# ESP_SmartWatch.net
KiCad netlist of a schematic drawn in EAGLE
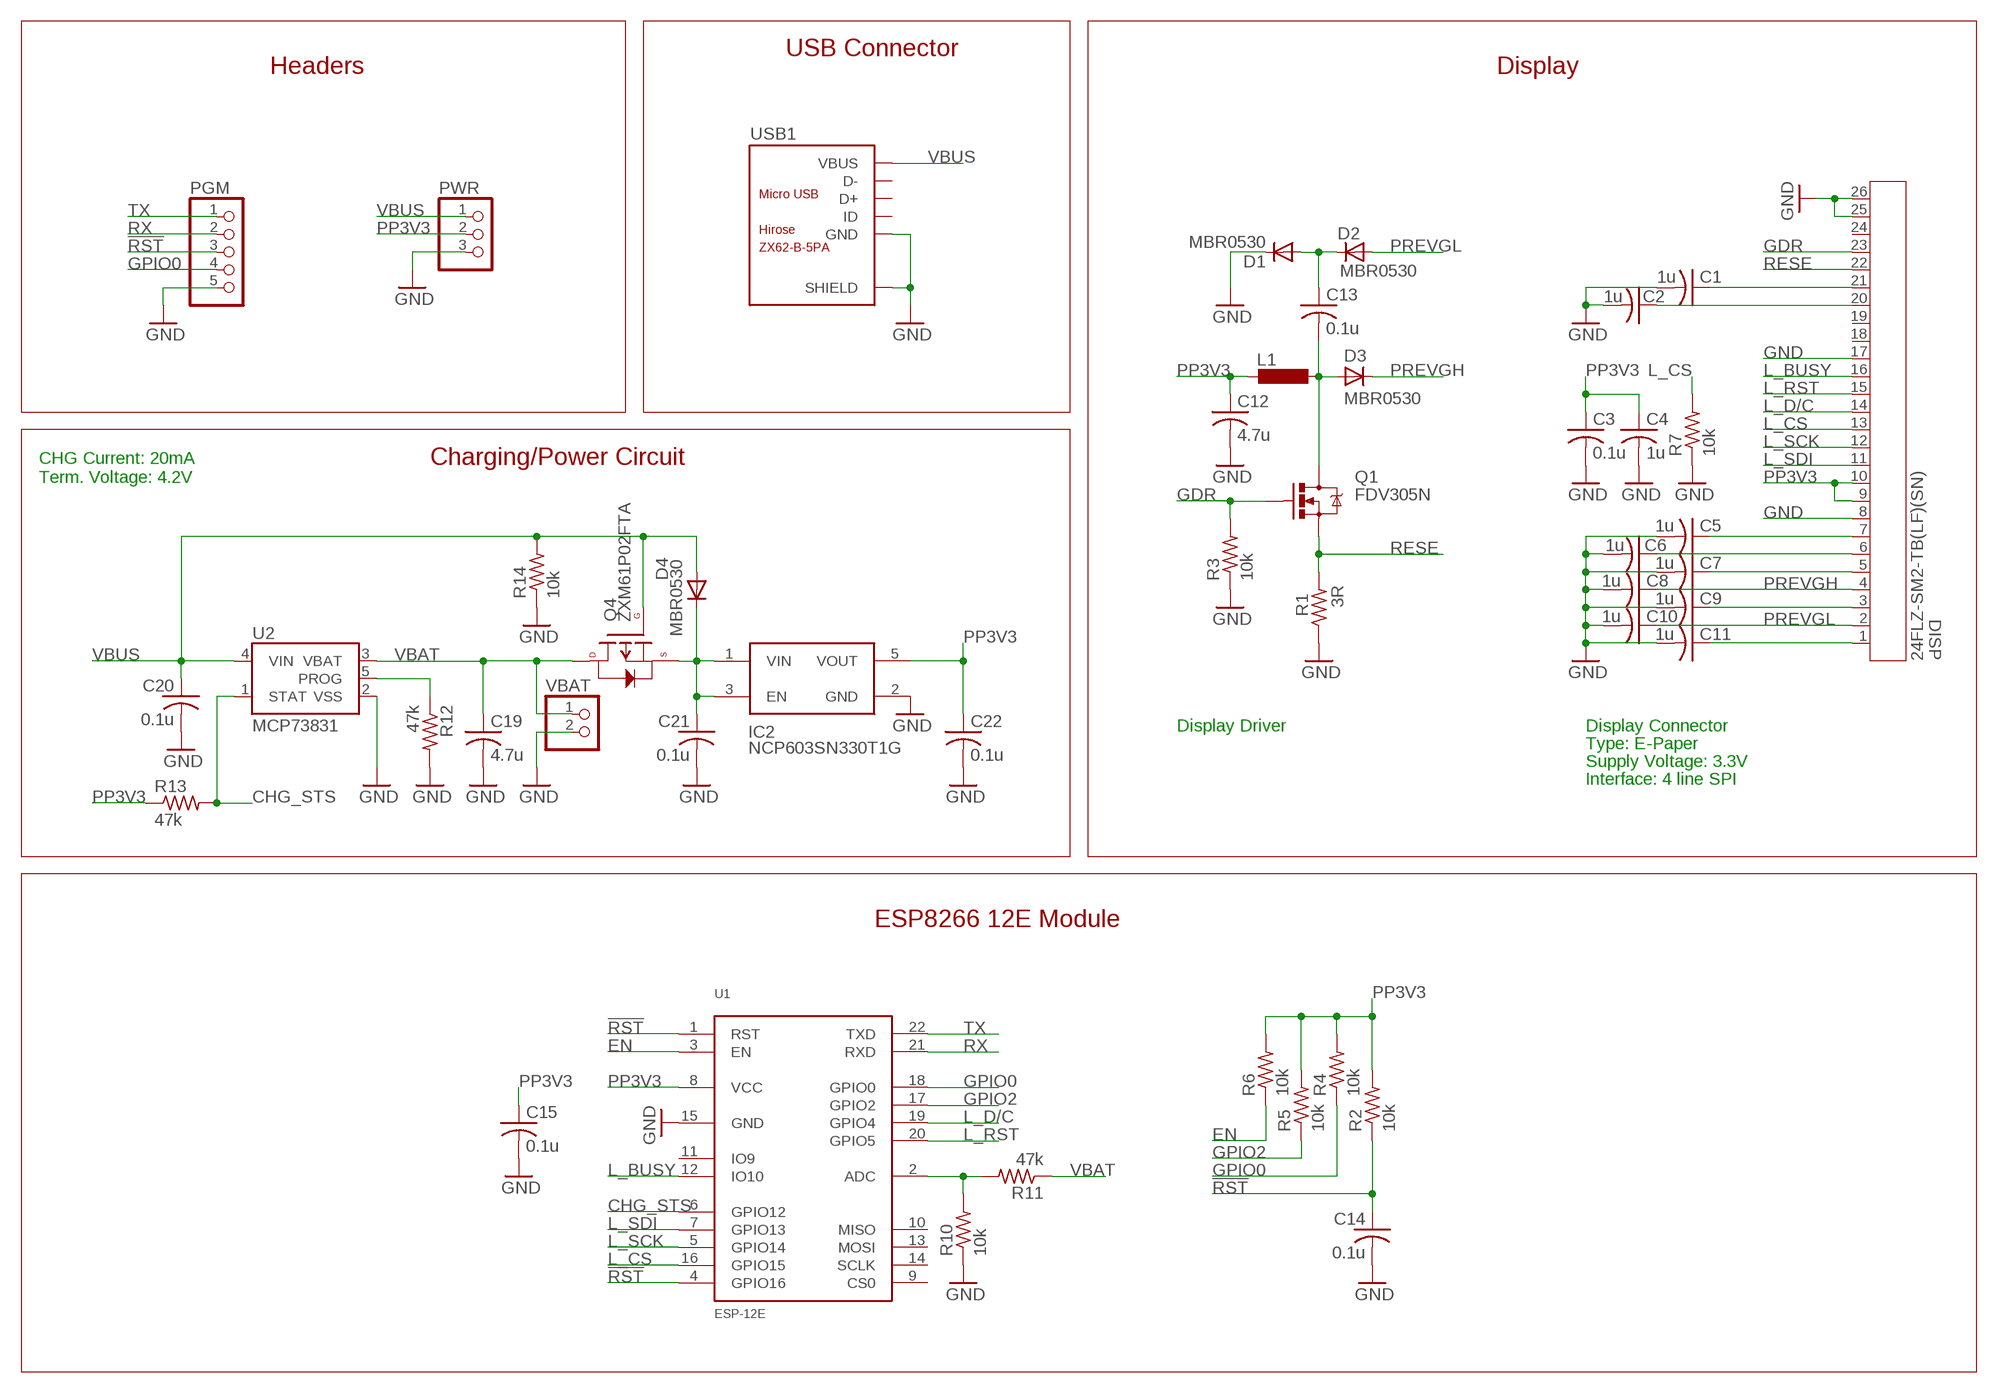
[diagram p0: schematic, sheet 1]

(export (version "E")
  (design (tool "Eeschema 10.0.6"))
  (components
    (comp (ref "C1")
      (value "1u")
      (footprint "eagle-import:C0603")
      (libsource (lib "eagle-import") (part "C-USC0603"))
    )
    (comp (ref "C2")
      (value "1u")
      (footprint "eagle-import:C0603")
      (libsource (lib "eagle-import") (part "C-USC0603"))
    )
    (comp (ref "C3")
      (value "0.1u")
      (footprint "eagle-import:C0603")
      (libsource (lib "eagle-import") (part "C-USC0603"))
    )
    (comp (ref "C4")
      (value "1u")
      (footprint "eagle-import:C0603")
      (libsource (lib "eagle-import") (part "C-USC0603"))
    )
    (comp (ref "C5")
      (value "1u")
      (footprint "eagle-import:C0603")
      (libsource (lib "eagle-import") (part "C-USC0603"))
    )
    (comp (ref "C6")
      (value "1u")
      (footprint "eagle-import:C0603")
      (libsource (lib "eagle-import") (part "C-USC0603"))
    )
    (comp (ref "C7")
      (value "1u")
      (footprint "eagle-import:C0603")
      (libsource (lib "eagle-import") (part "C-USC0603"))
    )
    (comp (ref "C8")
      (value "1u")
      (footprint "eagle-import:C0603")
      (libsource (lib "eagle-import") (part "C-USC0603"))
    )
    (comp (ref "C9")
      (value "1u")
      (footprint "eagle-import:C0603")
      (libsource (lib "eagle-import") (part "C-USC0603"))
    )
    (comp (ref "C10")
      (value "1u")
      (footprint "eagle-import:C0603")
      (libsource (lib "eagle-import") (part "C-USC0603"))
    )
    (comp (ref "C11")
      (value "1u")
      (footprint "eagle-import:C0603")
      (libsource (lib "eagle-import") (part "C-USC0603"))
    )
    (comp (ref "C12")
      (value "4.7u")
      (footprint "eagle-import:C0603")
      (libsource (lib "eagle-import") (part "C-USC0603"))
    )
    (comp (ref "C13")
      (value "0.1u")
      (footprint "eagle-import:C0603")
      (libsource (lib "eagle-import") (part "C-USC0603"))
    )
    (comp (ref "C14")
      (value "0.1u")
      (footprint "eagle-import:C0603")
      (libsource (lib "eagle-import") (part "C-USC0603"))
    )
    (comp (ref "C15")
      (value "0.1u")
      (footprint "eagle-import:C0603")
      (libsource (lib "eagle-import") (part "C-USC0603"))
    )
    (comp (ref "C19")
      (value "4.7u")
      (footprint "eagle-import:C0603")
      (libsource (lib "eagle-import") (part "C-USC0603"))
    )
    (comp (ref "C20")
      (value "0.1u")
      (footprint "eagle-import:C0603")
      (libsource (lib "eagle-import") (part "C-USC0603"))
    )
    (comp (ref "C21")
      (value "0.1u")
      (footprint "eagle-import:C0603")
      (libsource (lib "eagle-import") (part "C-USC0603"))
    )
    (comp (ref "C22")
      (value "0.1u")
      (footprint "eagle-import:C0603")
      (libsource (lib "eagle-import") (part "C-USC0603"))
    )
    (comp (ref "D1")
      (value "MBR0530")
      (footprint "eagle-import:SOD123")
      (libsource (lib "eagle-import") (part "MBR0520LT"))
    )
    (comp (ref "D2")
      (value "MBR0530")
      (footprint "eagle-import:SOD123")
      (libsource (lib "eagle-import") (part "MBR0520LT"))
    )
    (comp (ref "D3")
      (value "MBR0530")
      (footprint "eagle-import:SOD123")
      (libsource (lib "eagle-import") (part "MBR0520LT"))
    )
    (comp (ref "D4")
      (value "MBR0530")
      (footprint "eagle-import:SOD123")
      (libsource (lib "eagle-import") (part "MBR0520LT"))
    )
    (comp (ref "DISP")
      (value "24FLZ-SM2-TB(LF)(SN)")
      (footprint "eagle-import:CON24_1X24_DB_JST")
      (fields (field (name "MANUFACTURER_PART_NUMBER") "24FLZSM2TBLFSN"))
      (libsource (lib "eagle-import") (part "24FLZ-SM2-TB(LF)(SN)"))
    )
    (comp (ref "IC2")
      (value "NCP603SN330T1G")
      (footprint "eagle-import:SOT95P275X110-5N")
      (fields (field (name "RS_PART_NUMBER") "8051845P"))
      (libsource (lib "eagle-import") (part "NCP603SN330T1G"))
    )
    (comp (ref "L1")
      (value "ASPI-6045S-680M-T")
      (footprint "eagle-import:ASPI-6045S-680M-T")
      (libsource (lib "eagle-import") (part "ASPI-6045S-680M-T"))
    )
    (comp (ref "PGM")
      (value "PINHD-1X05_2.00")
      (footprint "eagle-import:1X05M")
      (libsource (lib "eagle-import") (part "PINHD-1X05_2.00"))
    )
    (comp (ref "PWR")
      (value "PINHD-1X03_2.00")
      (footprint "eagle-import:1X03M")
      (libsource (lib "eagle-import") (part "PINHD-1X03_2.00"))
    )
    (comp (ref "Q1")
      (value "FDV305N")
      (footprint "eagle-import:SOT23-3")
      (libsource (lib "eagle-import") (part "MOSFET-NCHANNELAO3404A"))
    )
    (comp (ref "Q4")
      (value "ZXM61P02FTA")
      (footprint "eagle-import:SOT23-3")
      (libsource (lib "eagle-import") (part "P-CHANNEL-MOSFET"))
    )
    (comp (ref "R1")
      (value "3R")
      (footprint "eagle-import:R0603")
      (libsource (lib "eagle-import") (part "R-US_R0603"))
    )
    (comp (ref "R2")
      (value "10k")
      (footprint "eagle-import:R0603")
      (libsource (lib "eagle-import") (part "R-US_R0603"))
    )
    (comp (ref "R3")
      (value "10k")
      (footprint "eagle-import:R0603")
      (libsource (lib "eagle-import") (part "R-US_R0603"))
    )
    (comp (ref "R4")
      (value "10k")
      (footprint "eagle-import:R0603")
      (libsource (lib "eagle-import") (part "R-US_R0603"))
    )
    (comp (ref "R5")
      (value "10k")
      (footprint "eagle-import:R0603")
      (libsource (lib "eagle-import") (part "R-US_R0603"))
    )
    (comp (ref "R6")
      (value "10k")
      (footprint "eagle-import:R0603")
      (libsource (lib "eagle-import") (part "R-US_R0603"))
    )
    (comp (ref "R7")
      (value "10k")
      (footprint "eagle-import:R0603")
      (libsource (lib "eagle-import") (part "R-US_R0603"))
    )
    (comp (ref "R10")
      (value "10k")
      (footprint "eagle-import:R0603")
      (libsource (lib "eagle-import") (part "R-US_R0603"))
    )
    (comp (ref "R11")
      (value "47k")
      (footprint "eagle-import:R0603")
      (libsource (lib "eagle-import") (part "R-US_R0603"))
    )
    (comp (ref "R12")
      (value "47k")
      (footprint "eagle-import:R0603")
      (libsource (lib "eagle-import") (part "R-US_R0603"))
    )
    (comp (ref "R13")
      (value "47k")
      (footprint "eagle-import:R0603")
      (libsource (lib "eagle-import") (part "R-US_R0603"))
    )
    (comp (ref "R14")
      (value "10k")
      (footprint "eagle-import:R0603")
      (libsource (lib "eagle-import") (part "R-US_R0603"))
    )
    (comp (ref "U1")
      (value "ESP-12E")
      (footprint "eagle-import:ESP-12F")
      (libsource (lib "eagle-import") (part "ESP-12F"))
    )
    (comp (ref "U2")
      (value "MCP73831")
      (footprint "eagle-import:SOT23-5")
      (libsource (lib "eagle-import") (part "MCP73831"))
    )
    (comp (ref "USB1")
      (value "ZX62-B-5PA")
      (footprint "eagle-import:MICRO-USB5+6P-SMD-0.65-AB")
      (libsource (lib "eagle-import") (part "MICRO-USB-SMD(ZX62-B-5PA)"))
    )
    (comp (ref "VBAT")
      (value "PINHD-1X02_2.00")
      (footprint "eagle-import:1X02M")
      (libsource (lib "eagle-import") (part "PINHD-1X02_2.00"))
    )
  )
  (nets
    (net (code "1") (name "/CHG_STS") (class "Default")
      (node (ref "R13") (pin "2") (pinfunction "2_2") (pintype "passive"))
      (node (ref "U1") (pin "6") (pinfunction "GPIO12_6") (pintype "bidirectional"))
      (node (ref "U2") (pin "1") (pinfunction "STAT_1") (pintype "output"))
    )
    (net (code "2") (name "/EN") (class "Default")
      (node (ref "R6") (pin "1") (pinfunction "1_1") (pintype "passive"))
      (node (ref "U1") (pin "3") (pinfunction "EN_3") (pintype "bidirectional"))
    )
    (net (code "3") (name "/GDR") (class "Default")
      (node (ref "DISP") (pin "23") (pinfunction "2323_23") (pintype "passive"))
      (node (ref "Q1") (pin "1") (pinfunction "G_1") (pintype "passive"))
      (node (ref "R3") (pin "2") (pinfunction "2_2") (pintype "passive"))
    )
    (net (code "4") (name "/GPIO0") (class "Default")
      (node (ref "PGM") (pin "4") (pinfunction "4_4") (pintype "passive"))
      (node (ref "R4") (pin "1") (pinfunction "1_1") (pintype "passive"))
      (node (ref "U1") (pin "18") (pinfunction "GPIO0_18") (pintype "bidirectional"))
    )
    (net (code "5") (name "/GPIO2") (class "Default")
      (node (ref "R5") (pin "1") (pinfunction "1_1") (pintype "passive"))
      (node (ref "U1") (pin "17") (pinfunction "GPIO2_17") (pintype "bidirectional"))
    )
    (net (code "6") (name "/L_BUSY") (class "Default")
      (node (ref "DISP") (pin "16") (pinfunction "1616_16") (pintype "passive"))
      (node (ref "U1") (pin "12") (pinfunction "IO10_12") (pintype "bidirectional"))
    )
    (net (code "7") (name "/L_CS") (class "Default")
      (node (ref "DISP") (pin "13") (pinfunction "1313_13") (pintype "passive"))
      (node (ref "R7") (pin "2") (pinfunction "2_2") (pintype "passive"))
      (node (ref "U1") (pin "16") (pinfunction "GPIO15_16") (pintype "bidirectional"))
    )
    (net (code "8") (name "/L_D{slash}C") (class "Default")
      (node (ref "DISP") (pin "14") (pinfunction "1414_14") (pintype "passive"))
      (node (ref "U1") (pin "19") (pinfunction "GPIO4_19") (pintype "bidirectional"))
    )
    (net (code "9") (name "/L_RST") (class "Default")
      (node (ref "DISP") (pin "15") (pinfunction "1515_15") (pintype "passive"))
      (node (ref "U1") (pin "20") (pinfunction "GPIO5_20") (pintype "bidirectional"))
    )
    (net (code "10") (name "/L_SCK") (class "Default")
      (node (ref "DISP") (pin "12") (pinfunction "1212_12") (pintype "passive"))
      (node (ref "U1") (pin "5") (pinfunction "GPIO14_5") (pintype "bidirectional"))
    )
    (net (code "11") (name "/L_SDI") (class "Default")
      (node (ref "DISP") (pin "11") (pinfunction "1111_11") (pintype "passive"))
      (node (ref "U1") (pin "7") (pinfunction "GPIO13_7") (pintype "bidirectional"))
    )
    (net (code "12") (name "/PP3V3") (class "Default")
      (node (ref "C12") (pin "1") (pinfunction "1_1") (pintype "passive"))
      (node (ref "C15") (pin "1") (pinfunction "1_1") (pintype "passive"))
      (node (ref "C22") (pin "1") (pinfunction "1_1") (pintype "passive"))
      (node (ref "C3") (pin "1") (pinfunction "1_1") (pintype "passive"))
      (node (ref "C4") (pin "1") (pinfunction "1_1") (pintype "passive"))
      (node (ref "DISP") (pin "10") (pinfunction "1010_10") (pintype "passive"))
      (node (ref "DISP") (pin "9") (pinfunction "99_9") (pintype "passive"))
      (node (ref "IC2") (pin "5") (pinfunction "VOUT_5") (pintype "output"))
      (node (ref "L1") (pin "1") (pinfunction "1_1") (pintype "passive"))
      (node (ref "PWR") (pin "2") (pinfunction "2_2") (pintype "passive"))
      (node (ref "R13") (pin "1") (pinfunction "1_1") (pintype "passive"))
      (node (ref "R2") (pin "2") (pinfunction "2_2") (pintype "passive"))
      (node (ref "R4") (pin "2") (pinfunction "2_2") (pintype "passive"))
      (node (ref "R5") (pin "2") (pinfunction "2_2") (pintype "passive"))
      (node (ref "R6") (pin "2") (pinfunction "2_2") (pintype "passive"))
      (node (ref "U1") (pin "8") (pinfunction "VCC_8") (pintype "bidirectional"))
    )
    (net (code "13") (name "/PREVGH") (class "Default")
      (node (ref "C8") (pin "1") (pinfunction "1_1") (pintype "passive"))
      (node (ref "D3") (pin "C") (pinfunction "C_C") (pintype "passive"))
      (node (ref "DISP") (pin "4") (pinfunction "44_4") (pintype "passive"))
    )
    (net (code "14") (name "/PREVGL") (class "Default")
      (node (ref "C10") (pin "1") (pinfunction "1_1") (pintype "passive"))
      (node (ref "D2") (pin "A") (pinfunction "A_A") (pintype "passive"))
      (node (ref "DISP") (pin "2") (pinfunction "22_2") (pintype "passive"))
    )
    (net (code "15") (name "/RESE") (class "Default")
      (node (ref "DISP") (pin "22") (pinfunction "2222_22") (pintype "passive"))
      (node (ref "Q1") (pin "2") (pinfunction "S_2") (pintype "passive"))
      (node (ref "R1") (pin "2") (pinfunction "2_2") (pintype "passive"))
    )
    (net (code "16") (name "/RX") (class "Default")
      (node (ref "PGM") (pin "2") (pinfunction "2_2") (pintype "passive"))
      (node (ref "U1") (pin "21") (pinfunction "RXD_21") (pintype "bidirectional"))
    )
    (net (code "17") (name "/TX") (class "Default")
      (node (ref "PGM") (pin "1") (pinfunction "1_1") (pintype "passive"))
      (node (ref "U1") (pin "22") (pinfunction "TXD_22") (pintype "bidirectional"))
    )
    (net (code "18") (name "/VBAT") (class "Default")
      (node (ref "C19") (pin "1") (pinfunction "1_1") (pintype "passive"))
      (node (ref "Q4") (pin "3") (pinfunction "D_3") (pintype "passive"))
      (node (ref "R11") (pin "1") (pinfunction "1_1") (pintype "passive"))
      (node (ref "U2") (pin "3") (pinfunction "VBAT_3") (pintype "power_in"))
      (node (ref "VBAT") (pin "1") (pinfunction "1_1") (pintype "passive"))
    )
    (net (code "19") (name "/VBUS") (class "Default")
      (node (ref "C20") (pin "1") (pinfunction "1_1") (pintype "passive"))
      (node (ref "D4") (pin "A") (pinfunction "A_A") (pintype "passive"))
      (node (ref "PWR") (pin "1") (pinfunction "1_1") (pintype "passive"))
      (node (ref "Q4") (pin "1") (pinfunction "G_1") (pintype "passive"))
      (node (ref "R14") (pin "2") (pinfunction "2_2") (pintype "passive"))
      (node (ref "U2") (pin "4") (pinfunction "VIN_4") (pintype "power_in"))
      (node (ref "USB1") (pin "1") (pinfunction "VBUS_1") (pintype "power_in"))
    )
    (net (code "20") (name "/~{RST}") (class "Default")
      (node (ref "C14") (pin "1") (pinfunction "1_1") (pintype "passive"))
      (node (ref "PGM") (pin "3") (pinfunction "3_3") (pintype "passive"))
      (node (ref "R2") (pin "1") (pinfunction "1_1") (pintype "passive"))
      (node (ref "U1") (pin "1") (pinfunction "RST_1") (pintype "bidirectional"))
      (node (ref "U1") (pin "4") (pinfunction "GPIO16_4") (pintype "bidirectional"))
    )
    (net (code "21") (name "GND") (class "Default")
      (node (ref "C1") (pin "2") (pinfunction "2_2") (pintype "passive"))
      (node (ref "C10") (pin "2") (pinfunction "2_2") (pintype "passive"))
      (node (ref "C11") (pin "2") (pinfunction "2_2") (pintype "passive"))
      (node (ref "C12") (pin "2") (pinfunction "2_2") (pintype "passive"))
      (node (ref "C14") (pin "2") (pinfunction "2_2") (pintype "passive"))
      (node (ref "C15") (pin "2") (pinfunction "2_2") (pintype "passive"))
      (node (ref "C19") (pin "2") (pinfunction "2_2") (pintype "passive"))
      (node (ref "C2") (pin "2") (pinfunction "2_2") (pintype "passive"))
      (node (ref "C20") (pin "2") (pinfunction "2_2") (pintype "passive"))
      (node (ref "C21") (pin "2") (pinfunction "2_2") (pintype "passive"))
      (node (ref "C22") (pin "2") (pinfunction "2_2") (pintype "passive"))
      (node (ref "C3") (pin "2") (pinfunction "2_2") (pintype "passive"))
      (node (ref "C4") (pin "2") (pinfunction "2_2") (pintype "passive"))
      (node (ref "C5") (pin "2") (pinfunction "2_2") (pintype "passive"))
      (node (ref "C6") (pin "2") (pinfunction "2_2") (pintype "passive"))
      (node (ref "C7") (pin "2") (pinfunction "2_2") (pintype "passive"))
      (node (ref "C8") (pin "2") (pinfunction "2_2") (pintype "passive"))
      (node (ref "C9") (pin "2") (pinfunction "2_2") (pintype "passive"))
      (node (ref "D1") (pin "C") (pinfunction "C_C") (pintype "passive"))
      (node (ref "DISP") (pin "17") (pinfunction "1717_17") (pintype "passive"))
      (node (ref "DISP") (pin "25") (pinfunction "2525_25") (pintype "passive"))
      (node (ref "DISP") (pin "26") (pinfunction "2626_26") (pintype "passive"))
      (node (ref "DISP") (pin "8") (pinfunction "88_8") (pintype "passive"))
      (node (ref "IC2") (pin "2") (pinfunction "GND_2") (pintype "power_in"))
      (node (ref "PGM") (pin "5") (pinfunction "5_5") (pintype "passive"))
      (node (ref "PWR") (pin "3") (pinfunction "3_3") (pintype "passive"))
      (node (ref "R1") (pin "1") (pinfunction "1_1") (pintype "passive"))
      (node (ref "R10") (pin "1") (pinfunction "1_1") (pintype "passive"))
      (node (ref "R12") (pin "2") (pinfunction "2_2") (pintype "passive"))
      (node (ref "R14") (pin "1") (pinfunction "1_1") (pintype "passive"))
      (node (ref "R3") (pin "1") (pinfunction "1_1") (pintype "passive"))
      (node (ref "R7") (pin "1") (pinfunction "1_1") (pintype "passive"))
      (node (ref "U1") (pin "15") (pinfunction "GND_15") (pintype "bidirectional"))
      (node (ref "U2") (pin "2") (pinfunction "VSS_2") (pintype "power_in"))
      (node (ref "USB1") (pin "5") (pinfunction "GND_5") (pintype "power_in"))
      (node (ref "USB1") (pin "P1") (pinfunction "SHIELD_P1") (pintype "power_in"))
      (node (ref "USB1") (pin "P2") (pinfunction "SHIELD_P2") (pintype "power_in"))
      (node (ref "USB1") (pin "P3_1") (pinfunction "SHIELD_P3_1") (pintype "power_in"))
      (node (ref "USB1") (pin "P3_2") (pinfunction "SHIELD_P3_2") (pintype "power_in"))
      (node (ref "USB1") (pin "P3_3") (pinfunction "SHIELD_P3_3") (pintype "power_in"))
      (node (ref "USB1") (pin "P4_1") (pinfunction "SHIELD_P4_1") (pintype "power_in"))
      (node (ref "USB1") (pin "P4_2") (pinfunction "SHIELD_P4_2") (pintype "power_in"))
      (node (ref "USB1") (pin "P4_3") (pinfunction "SHIELD_P4_3") (pintype "power_in"))
      (node (ref "USB1") (pin "P5") (pinfunction "SHIELD_P5") (pintype "power_in"))
      (node (ref "USB1") (pin "P6") (pinfunction "SHIELD_P6") (pintype "power_in"))
      (node (ref "VBAT") (pin "2") (pinfunction "2_2") (pintype "passive"))
    )
    (net (code "22") (name "Net-(C13-Pad1)") (class "Default")
      (node (ref "C13") (pin "1") (pinfunction "1_1") (pintype "passive"))
      (node (ref "D1") (pin "A") (pinfunction "A_A") (pintype "passive"))
      (node (ref "D2") (pin "C") (pinfunction "C_C") (pintype "passive"))
    )
    (net (code "23") (name "Net-(DISP-11)") (class "Default")
      (node (ref "C11") (pin "1") (pinfunction "1_1") (pintype "passive"))
      (node (ref "DISP") (pin "1") (pinfunction "11_1") (pintype "passive"))
    )
    (net (code "24") (name "Net-(DISP-33)") (class "Default")
      (node (ref "C9") (pin "1") (pinfunction "1_1") (pintype "passive"))
      (node (ref "DISP") (pin "3") (pinfunction "33_3") (pintype "passive"))
    )
    (net (code "25") (name "Net-(DISP-55)") (class "Default")
      (node (ref "C7") (pin "1") (pinfunction "1_1") (pintype "passive"))
      (node (ref "DISP") (pin "5") (pinfunction "55_5") (pintype "passive"))
    )
    (net (code "26") (name "Net-(DISP-66)") (class "Default")
      (node (ref "C6") (pin "1") (pinfunction "1_1") (pintype "passive"))
      (node (ref "DISP") (pin "6") (pinfunction "66_6") (pintype "passive"))
    )
    (net (code "27") (name "Net-(DISP-77)") (class "Default")
      (node (ref "C5") (pin "1") (pinfunction "1_1") (pintype "passive"))
      (node (ref "DISP") (pin "7") (pinfunction "77_7") (pintype "passive"))
    )
    (net (code "28") (name "Net-(DISP-2020)") (class "Default")
      (node (ref "C2") (pin "1") (pinfunction "1_1") (pintype "passive"))
      (node (ref "DISP") (pin "20") (pinfunction "2020_20") (pintype "passive"))
    )
    (net (code "29") (name "Net-(DISP-2121)") (class "Default")
      (node (ref "C1") (pin "1") (pinfunction "1_1") (pintype "passive"))
      (node (ref "DISP") (pin "21") (pinfunction "2121_21") (pintype "passive"))
    )
    (net (code "30") (name "Net-(IC2-EN)") (class "Default")
      (node (ref "C21") (pin "1") (pinfunction "1_1") (pintype "passive"))
      (node (ref "D4") (pin "C") (pinfunction "C_C") (pintype "passive"))
      (node (ref "IC2") (pin "1") (pinfunction "VIN_1") (pintype "input"))
      (node (ref "IC2") (pin "3") (pinfunction "EN_3") (pintype "bidirectional"))
      (node (ref "Q4") (pin "2") (pinfunction "S_2") (pintype "passive"))
    )
    (net (code "31") (name "Net-(Q1-D)") (class "Default")
      (node (ref "C13") (pin "2") (pinfunction "2_2") (pintype "passive"))
      (node (ref "D3") (pin "A") (pinfunction "A_A") (pintype "passive"))
      (node (ref "L1") (pin "2") (pinfunction "2_2") (pintype "passive"))
      (node (ref "Q1") (pin "3") (pinfunction "D_3") (pintype "passive"))
    )
    (net (code "32") (name "Net-(U1-ADC)") (class "Default")
      (node (ref "R10") (pin "2") (pinfunction "2_2") (pintype "passive"))
      (node (ref "R11") (pin "2") (pinfunction "2_2") (pintype "passive"))
      (node (ref "U1") (pin "2") (pinfunction "ADC_2") (pintype "bidirectional"))
    )
    (net (code "33") (name "Net-(U2-PROG)") (class "Default")
      (node (ref "R12") (pin "1") (pinfunction "1_1") (pintype "passive"))
      (node (ref "U2") (pin "5") (pinfunction "PROG_5") (pintype "input"))
    )
    (net (code "34") (name "unconnected-(DISP-1818-Pad18)") (class "Default")
      (node (ref "DISP") (pin "18") (pinfunction "1818_18") (pintype "passive"))
    )
    (net (code "35") (name "unconnected-(DISP-1919-Pad19)") (class "Default")
      (node (ref "DISP") (pin "19") (pinfunction "1919_19") (pintype "passive"))
    )
    (net (code "36") (name "unconnected-(DISP-2424-Pad24)") (class "Default")
      (node (ref "DISP") (pin "24") (pinfunction "2424_24") (pintype "passive"))
    )
    (net (code "37") (name "unconnected-(U1-CS0-Pad9)") (class "Default")
      (node (ref "U1") (pin "9") (pinfunction "CS0_9") (pintype "bidirectional"))
    )
    (net (code "38") (name "unconnected-(U1-IO9-Pad11)") (class "Default")
      (node (ref "U1") (pin "11") (pinfunction "IO9_11") (pintype "bidirectional"))
    )
    (net (code "39") (name "unconnected-(U1-MISO-Pad10)") (class "Default")
      (node (ref "U1") (pin "10") (pinfunction "MISO_10") (pintype "bidirectional"))
    )
    (net (code "40") (name "unconnected-(U1-MOSI-Pad13)") (class "Default")
      (node (ref "U1") (pin "13") (pinfunction "MOSI_13") (pintype "bidirectional"))
    )
    (net (code "41") (name "unconnected-(U1-SCLK-Pad14)") (class "Default")
      (node (ref "U1") (pin "14") (pinfunction "SCLK_14") (pintype "bidirectional"))
    )
    (net (code "42") (name "unconnected-(USB1-D+-Pad3)") (class "Default")
      (node (ref "USB1") (pin "3") (pinfunction "D+_3") (pintype "bidirectional"))
    )
    (net (code "43") (name "unconnected-(USB1-D--Pad2)") (class "Default")
      (node (ref "USB1") (pin "2") (pinfunction "D-_2") (pintype "bidirectional"))
    )
    (net (code "44") (name "unconnected-(USB1-ID-Pad4)") (class "Default")
      (node (ref "USB1") (pin "4") (pinfunction "ID_4") (pintype "bidirectional"))
    )
  )
)
